# DeadHorsePCB_REV-A.net
KiCad netlist of a schematic drawn in EAGLE
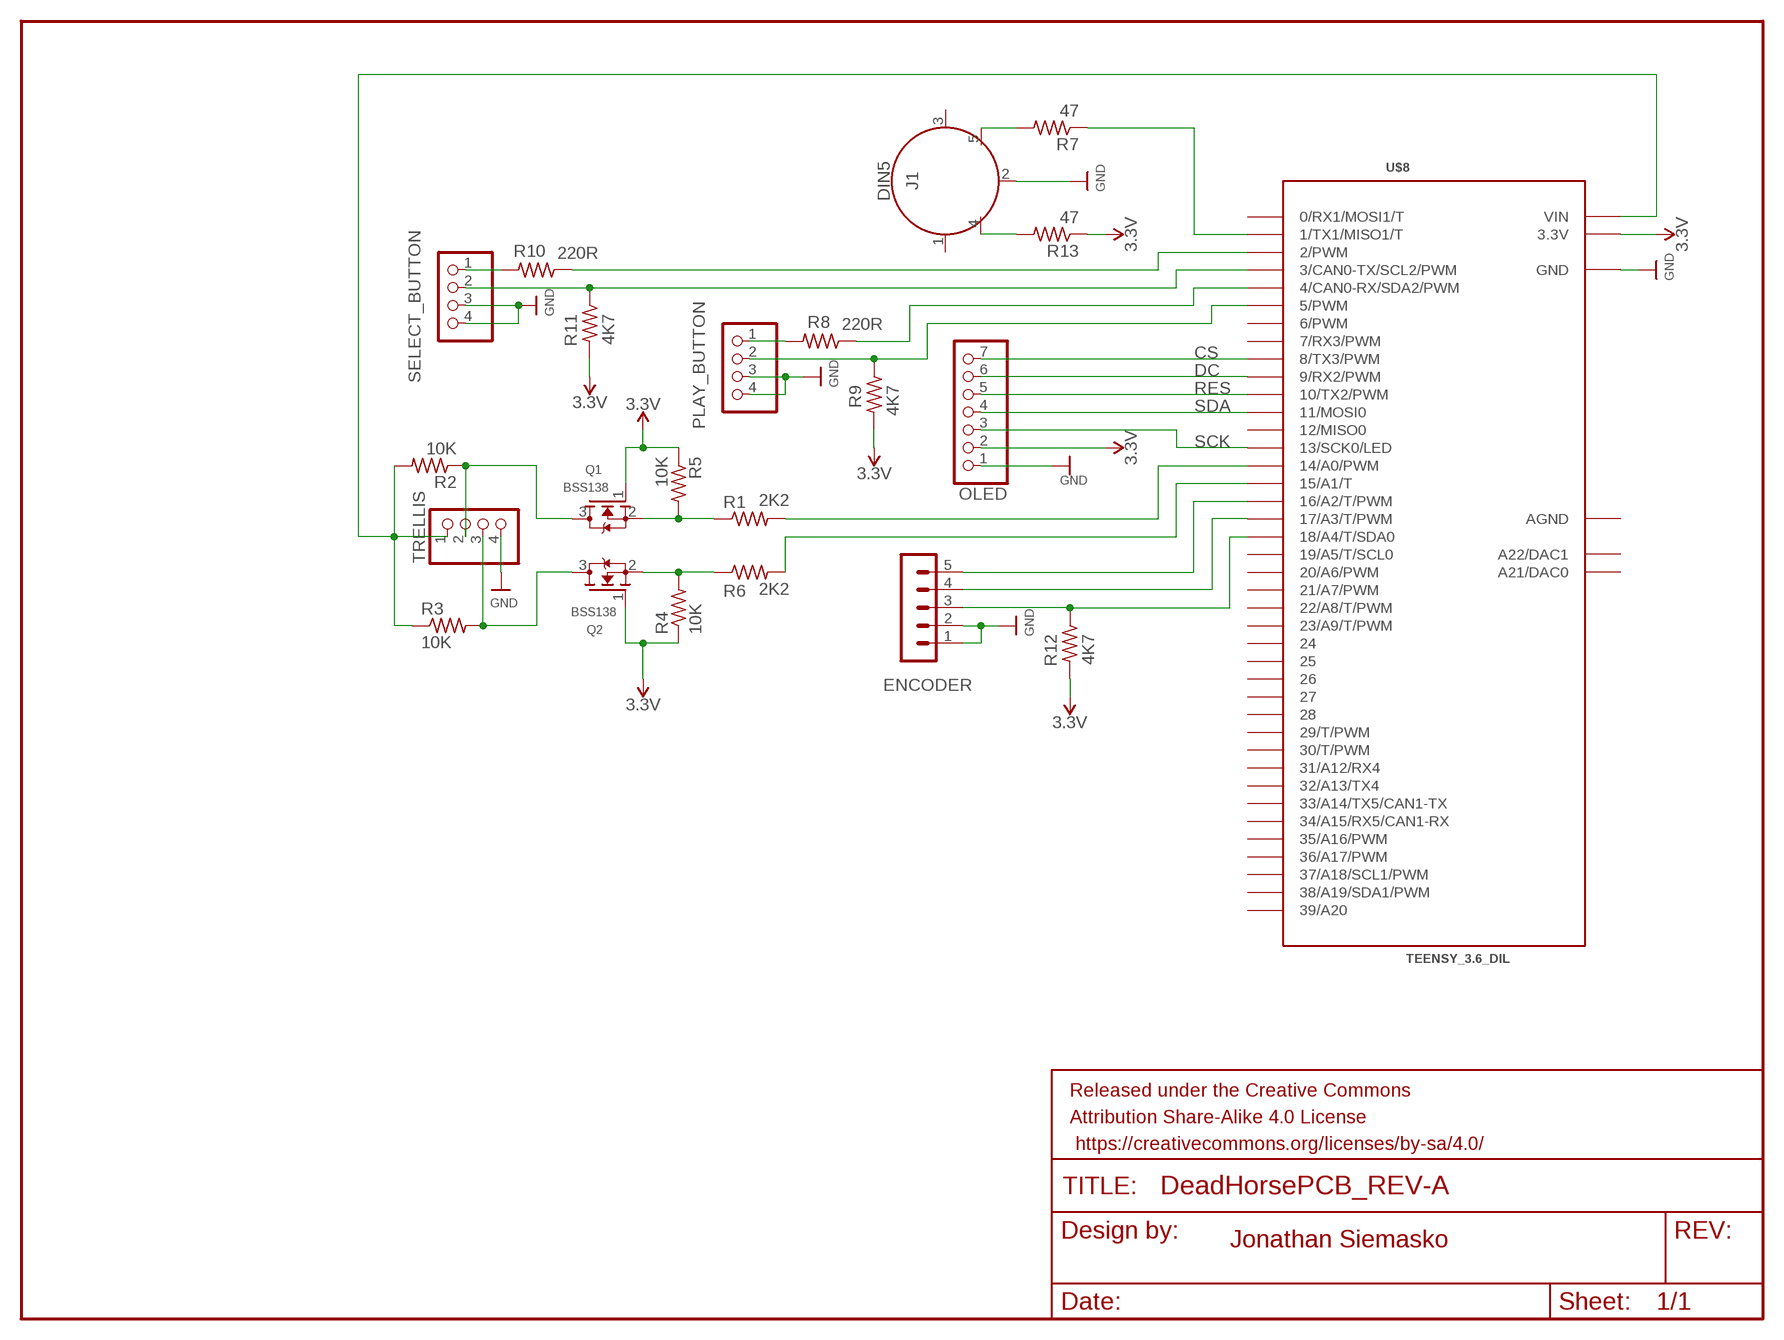
[diagram p0: schematic, sheet 1]

(export (version "E")
  (design (tool "Eeschema 10.0.6"))
  (components
    (comp (ref "ENCODER")
      (value "ENCODER")
      (footprint "eagle-import:MA05-1")
      (libsource (lib "eagle-import") (part "MA05-1"))
    )
    (comp (ref "FRAME1")
      (value "FRAME-LETTER")
      (footprint "eagle-import:CREATIVE_COMMONS")
      (libsource (lib "eagle-import") (part "FRAME-LETTER"))
    )
    (comp (ref "J1")
      (value "DIN5")
      (footprint "eagle-import:DIN5-RA-PTH")
      (libsource (lib "eagle-import") (part "DIN5"))
    )
    (comp (ref "OLED")
      (value "OLED")
      (footprint "eagle-import:1X07")
      (libsource (lib "eagle-import") (part "PINHD-1X7"))
    )
    (comp (ref "PLAY_BUTTON")
      (value "PlayBtn")
      (footprint "eagle-import:1X04")
      (libsource (lib "eagle-import") (part "PINHD-1X4"))
    )
    (comp (ref "Q1")
      (value "BSS138")
      (footprint "eagle-import:SOT23")
      (libsource (lib "eagle-import") (part "MOSFET-NREFLOW"))
    )
    (comp (ref "Q2")
      (value "BSS138")
      (footprint "eagle-import:SOT23")
      (libsource (lib "eagle-import") (part "MOSFET-NREFLOW"))
    )
    (comp (ref "R1")
      (value "2K2")
      (footprint "eagle-import:R0805")
      (libsource (lib "eagle-import") (part "R-US_R0805"))
    )
    (comp (ref "R2")
      (value "10K")
      (footprint "eagle-import:R0805")
      (libsource (lib "eagle-import") (part "R-US_R0805"))
    )
    (comp (ref "R3")
      (value "10K")
      (footprint "eagle-import:R0805")
      (libsource (lib "eagle-import") (part "R-US_R0805"))
    )
    (comp (ref "R4")
      (value "10K")
      (footprint "eagle-import:R0805")
      (libsource (lib "eagle-import") (part "R-US_R0805"))
    )
    (comp (ref "R5")
      (value "10K")
      (footprint "eagle-import:R0805")
      (libsource (lib "eagle-import") (part "R-US_R0805"))
    )
    (comp (ref "R6")
      (value "2K2")
      (footprint "eagle-import:R0805")
      (libsource (lib "eagle-import") (part "R-US_R0805"))
    )
    (comp (ref "R7")
      (value "47")
      (footprint "eagle-import:R0805")
      (libsource (lib "eagle-import") (part "R-US_R0805"))
    )
    (comp (ref "R8")
      (value "220R")
      (footprint "eagle-import:R0805")
      (libsource (lib "eagle-import") (part "R-US_R0805"))
    )
    (comp (ref "R9")
      (value "4K7")
      (footprint "eagle-import:R0805")
      (libsource (lib "eagle-import") (part "R-US_R0805"))
    )
    (comp (ref "R10")
      (value "220R")
      (footprint "eagle-import:R0805")
      (libsource (lib "eagle-import") (part "R-US_R0805"))
    )
    (comp (ref "R11")
      (value "4K7")
      (footprint "eagle-import:R0805")
      (libsource (lib "eagle-import") (part "R-US_R0805"))
    )
    (comp (ref "R12")
      (value "4K7")
      (footprint "eagle-import:R0805")
      (libsource (lib "eagle-import") (part "R-US_R0805"))
    )
    (comp (ref "R13")
      (value "47")
      (footprint "eagle-import:R0805")
      (libsource (lib "eagle-import") (part "R-US_R0805"))
    )
    (comp (ref "SELECT_BUTTON")
      (value "SelectBtn")
      (footprint "eagle-import:1X04")
      (libsource (lib "eagle-import") (part "PINHD-1X4"))
    )
    (comp (ref "TRELLIS")
      (value "TRELLIS")
      (footprint "eagle-import:1X04")
      (libsource (lib "eagle-import") (part "PINHD-1X4"))
    )
    (comp (ref "U$8")
      (value "TEENSY_3.6_DIL")
      (footprint "eagle-import:TEENSY_3.6_DIL")
      (libsource (lib "eagle-import") (part "TEENSY_3.6_DIL"))
    )
  )
  (nets
    (net (code "1") (name "/AGND") (class "Default")
      (node (ref "U$8") (pin "AGND") (pinfunction "AGND_AGND") (pintype "power_in"))
    )
    (net (code "2") (name "/CS") (class "Default")
      (node (ref "OLED") (pin "7") (pinfunction "7_7") (pintype "passive"))
      (node (ref "U$8") (pin "8") (pinfunction "8/TX3/PWM_8") (pintype "bidirectional"))
    )
    (net (code "3") (name "/DC") (class "Default")
      (node (ref "OLED") (pin "6") (pinfunction "6_6") (pintype "passive"))
      (node (ref "U$8") (pin "9") (pinfunction "9/RX2/PWM_9") (pintype "bidirectional"))
    )
    (net (code "4") (name "/RES") (class "Default")
      (node (ref "OLED") (pin "5") (pinfunction "5_5") (pintype "passive"))
      (node (ref "U$8") (pin "10") (pinfunction "10/TX2/PWM_10") (pintype "bidirectional"))
    )
    (net (code "5") (name "/SCK") (class "Default")
      (node (ref "OLED") (pin "3") (pinfunction "3_3") (pintype "passive"))
      (node (ref "U$8") (pin "13") (pinfunction "13/SCK0/LED_13") (pintype "bidirectional"))
    )
    (net (code "6") (name "/SDA") (class "Default")
      (node (ref "OLED") (pin "4") (pinfunction "4_4") (pintype "passive"))
      (node (ref "U$8") (pin "11") (pinfunction "11/MOSI0_11") (pintype "bidirectional"))
    )
    (net (code "7") (name "3.3V") (class "Default")
      (node (ref "OLED") (pin "2") (pinfunction "2_2") (pintype "passive"))
      (node (ref "Q1") (pin "1") (pinfunction "G_1") (pintype "bidirectional"))
      (node (ref "Q2") (pin "1") (pinfunction "G_1") (pintype "bidirectional"))
      (node (ref "R11") (pin "2") (pinfunction "2_2") (pintype "passive"))
      (node (ref "R12") (pin "2") (pinfunction "2_2") (pintype "passive"))
      (node (ref "R13") (pin "1") (pinfunction "1_1") (pintype "passive"))
      (node (ref "R4") (pin "1") (pinfunction "1_1") (pintype "passive"))
      (node (ref "R5") (pin "1") (pinfunction "1_1") (pintype "passive"))
      (node (ref "R9") (pin "2") (pinfunction "2_2") (pintype "passive"))
      (node (ref "U$8") (pin "3.3V") (pinfunction "3.3V_3.3V") (pintype "power_in"))
      (node (ref "U$8") (pin "3.3V3") (pinfunction "3.3V_3.3V3") (pintype "power_in"))
    )
    (net (code "8") (name "GND") (class "Default")
      (node (ref "ENCODER") (pin "1") (pinfunction "1_1") (pintype "passive"))
      (node (ref "ENCODER") (pin "2") (pinfunction "2_2") (pintype "passive"))
      (node (ref "J1") (pin "2") (pinfunction "2_2") (pintype "bidirectional"))
      (node (ref "OLED") (pin "1") (pinfunction "1_1") (pintype "passive"))
      (node (ref "PLAY_BUTTON") (pin "3") (pinfunction "3_3") (pintype "passive"))
      (node (ref "PLAY_BUTTON") (pin "4") (pinfunction "4_4") (pintype "passive"))
      (node (ref "SELECT_BUTTON") (pin "3") (pinfunction "3_3") (pintype "passive"))
      (node (ref "SELECT_BUTTON") (pin "4") (pinfunction "4_4") (pintype "passive"))
      (node (ref "TRELLIS") (pin "4") (pinfunction "4_4") (pintype "passive"))
      (node (ref "U$8") (pin "GND") (pinfunction "GND_GND") (pintype "power_in"))
      (node (ref "U$8") (pin "GND1") (pinfunction "GND_GND1") (pintype "power_in"))
    )
    (net (code "9") (name "Net-(J1-Pad4)") (class "Default")
      (node (ref "J1") (pin "4") (pinfunction "4_4") (pintype "bidirectional"))
      (node (ref "R13") (pin "2") (pinfunction "2_2") (pintype "passive"))
    )
    (net (code "10") (name "Net-(J1-Pad5)") (class "Default")
      (node (ref "J1") (pin "5") (pinfunction "5_5") (pintype "bidirectional"))
      (node (ref "R7") (pin "2") (pinfunction "2_2") (pintype "passive"))
    )
    (net (code "11") (name "Net-(PLAY_BUTTON-Pad1)") (class "Default")
      (node (ref "PLAY_BUTTON") (pin "1") (pinfunction "1_1") (pintype "passive"))
      (node (ref "R8") (pin "2") (pinfunction "2_2") (pintype "passive"))
    )
    (net (code "12") (name "Net-(Q1-D)") (class "Default")
      (node (ref "Q1") (pin "3") (pinfunction "D_3") (pintype "bidirectional"))
      (node (ref "R2") (pin "1") (pinfunction "1_1") (pintype "passive"))
      (node (ref "TRELLIS") (pin "2") (pinfunction "2_2") (pintype "passive"))
    )
    (net (code "13") (name "Net-(Q1-S)") (class "Default")
      (node (ref "Q1") (pin "2") (pinfunction "S_2") (pintype "bidirectional"))
      (node (ref "R1") (pin "1") (pinfunction "1_1") (pintype "passive"))
      (node (ref "R5") (pin "2") (pinfunction "2_2") (pintype "passive"))
    )
    (net (code "14") (name "Net-(Q2-D)") (class "Default")
      (node (ref "Q2") (pin "3") (pinfunction "D_3") (pintype "bidirectional"))
      (node (ref "R3") (pin "2") (pinfunction "2_2") (pintype "passive"))
      (node (ref "TRELLIS") (pin "3") (pinfunction "3_3") (pintype "passive"))
    )
    (net (code "15") (name "Net-(Q2-S)") (class "Default")
      (node (ref "Q2") (pin "2") (pinfunction "S_2") (pintype "bidirectional"))
      (node (ref "R4") (pin "2") (pinfunction "2_2") (pintype "passive"))
      (node (ref "R6") (pin "1") (pinfunction "1_1") (pintype "passive"))
    )
    (net (code "16") (name "Net-(R2-Pad2)") (class "Default")
      (node (ref "R2") (pin "2") (pinfunction "2_2") (pintype "passive"))
      (node (ref "R3") (pin "1") (pinfunction "1_1") (pintype "passive"))
      (node (ref "TRELLIS") (pin "1") (pinfunction "1_1") (pintype "passive"))
      (node (ref "U$8") (pin "VIN") (pinfunction "VIN_VIN") (pintype "power_in"))
    )
    (net (code "17") (name "Net-(R10-Pad2)") (class "Default")
      (node (ref "R10") (pin "2") (pinfunction "2_2") (pintype "passive"))
      (node (ref "SELECT_BUTTON") (pin "1") (pinfunction "1_1") (pintype "passive"))
    )
    (net (code "18") (name "Net-(U$8-1{slash}TX1{slash}MISO1{slash}T)") (class "Default")
      (node (ref "R7") (pin "1") (pinfunction "1_1") (pintype "passive"))
      (node (ref "U$8") (pin "1") (pinfunction "1/TX1/MISO1/T_1") (pintype "bidirectional"))
    )
    (net (code "19") (name "Net-(U$8-2{slash}PWM)") (class "Default")
      (node (ref "R10") (pin "1") (pinfunction "1_1") (pintype "passive"))
      (node (ref "U$8") (pin "2") (pinfunction "2/PWM_2") (pintype "bidirectional"))
    )
    (net (code "20") (name "Net-(U$8-3{slash}CAN0-TX{slash}SCL2{slash}PWM)") (class "Default")
      (node (ref "R11") (pin "1") (pinfunction "1_1") (pintype "passive"))
      (node (ref "SELECT_BUTTON") (pin "2") (pinfunction "2_2") (pintype "passive"))
      (node (ref "U$8") (pin "3") (pinfunction "3/CAN0-TX/SCL2/PWM_3") (pintype "bidirectional"))
    )
    (net (code "21") (name "Net-(U$8-4{slash}CAN0-RX{slash}SDA2{slash}PWM)") (class "Default")
      (node (ref "R8") (pin "1") (pinfunction "1_1") (pintype "passive"))
      (node (ref "U$8") (pin "4") (pinfunction "4/CAN0-RX/SDA2/PWM_4") (pintype "bidirectional"))
    )
    (net (code "22") (name "Net-(U$8-5{slash}PWM)") (class "Default")
      (node (ref "PLAY_BUTTON") (pin "2") (pinfunction "2_2") (pintype "passive"))
      (node (ref "R9") (pin "1") (pinfunction "1_1") (pintype "passive"))
      (node (ref "U$8") (pin "5") (pinfunction "5/PWM_5") (pintype "bidirectional"))
    )
    (net (code "23") (name "Net-(U$8-14{slash}A0{slash}PWM)") (class "Default")
      (node (ref "R1") (pin "2") (pinfunction "2_2") (pintype "passive"))
      (node (ref "U$8") (pin "14/A0") (pinfunction "14/A0/PWM_14/A0") (pintype "bidirectional"))
    )
    (net (code "24") (name "Net-(U$8-15{slash}A1{slash}T)") (class "Default")
      (node (ref "R6") (pin "2") (pinfunction "2_2") (pintype "passive"))
      (node (ref "U$8") (pin "15/A1") (pinfunction "15/A1/T_15/A1") (pintype "bidirectional"))
    )
    (net (code "25") (name "Net-(U$8-16{slash}A2{slash}T{slash}PWM)") (class "Default")
      (node (ref "ENCODER") (pin "5") (pinfunction "5_5") (pintype "passive"))
      (node (ref "U$8") (pin "16/A2") (pinfunction "16/A2/T/PWM_16/A2") (pintype "bidirectional"))
    )
    (net (code "26") (name "Net-(U$8-17{slash}A3{slash}T{slash}PWM)") (class "Default")
      (node (ref "ENCODER") (pin "4") (pinfunction "4_4") (pintype "passive"))
      (node (ref "U$8") (pin "17/A3") (pinfunction "17/A3/T/PWM_17/A3") (pintype "bidirectional"))
    )
    (net (code "27") (name "Net-(U$8-18{slash}A4{slash}T{slash}SDA0)") (class "Default")
      (node (ref "ENCODER") (pin "3") (pinfunction "3_3") (pintype "passive"))
      (node (ref "R12") (pin "1") (pinfunction "1_1") (pintype "passive"))
      (node (ref "U$8") (pin "18/A4") (pinfunction "18/A4/T/SDA0_18/A4") (pintype "bidirectional"))
    )
    (net (code "28") (name "unconnected-(J1-Pad1)") (class "Default")
      (node (ref "J1") (pin "1") (pinfunction "1_1") (pintype "bidirectional"))
    )
    (net (code "29") (name "unconnected-(J1-Pad3)") (class "Default")
      (node (ref "J1") (pin "3") (pinfunction "3_3") (pintype "bidirectional"))
    )
    (net (code "30") (name "unconnected-(U$8-0{slash}RX1{slash}MOSI1{slash}T-Pad0)") (class "Default")
      (node (ref "U$8") (pin "0") (pinfunction "0/RX1/MOSI1/T_0") (pintype "bidirectional"))
    )
    (net (code "31") (name "unconnected-(U$8-6{slash}PWM-Pad6)") (class "Default")
      (node (ref "U$8") (pin "6") (pinfunction "6/PWM_6") (pintype "bidirectional"))
    )
    (net (code "32") (name "unconnected-(U$8-7{slash}RX3{slash}PWM-Pad7)") (class "Default")
      (node (ref "U$8") (pin "7") (pinfunction "7/RX3/PWM_7") (pintype "bidirectional"))
    )
    (net (code "33") (name "unconnected-(U$8-12{slash}MISO0-Pad12)") (class "Default")
      (node (ref "U$8") (pin "12") (pinfunction "12/MISO0_12") (pintype "bidirectional"))
    )
    (net (code "34") (name "unconnected-(U$8-19{slash}A5{slash}T{slash}SCL0-Pad19{slash}A5)") (class "Default")
      (node (ref "U$8") (pin "19/A5") (pinfunction "19/A5/T/SCL0_19/A5") (pintype "bidirectional"))
    )
    (net (code "35") (name "unconnected-(U$8-20{slash}A6{slash}PWM-Pad20{slash}A6)") (class "Default")
      (node (ref "U$8") (pin "20/A6") (pinfunction "20/A6/PWM_20/A6") (pintype "bidirectional"))
    )
    (net (code "36") (name "unconnected-(U$8-21{slash}A7{slash}PWM-Pad21{slash}A7)") (class "Default")
      (node (ref "U$8") (pin "21/A7") (pinfunction "21/A7/PWM_21/A7") (pintype "bidirectional"))
    )
    (net (code "37") (name "unconnected-(U$8-22{slash}A8{slash}T{slash}PWM-Pad22{slash}A8)") (class "Default")
      (node (ref "U$8") (pin "22/A8") (pinfunction "22/A8/T/PWM_22/A8") (pintype "bidirectional"))
    )
    (net (code "38") (name "unconnected-(U$8-23{slash}A9{slash}T{slash}PWM-Pad23{slash}A9)") (class "Default")
      (node (ref "U$8") (pin "23/A9") (pinfunction "23/A9/T/PWM_23/A9") (pintype "bidirectional"))
    )
    (net (code "39") (name "unconnected-(U$8-29{slash}T{slash}PWM-Pad29)") (class "Default")
      (node (ref "U$8") (pin "29") (pinfunction "29/T/PWM_29") (pintype "bidirectional"))
    )
    (net (code "40") (name "unconnected-(U$8-30{slash}T{slash}PWM-Pad30)") (class "Default")
      (node (ref "U$8") (pin "30") (pinfunction "30/T/PWM_30") (pintype "bidirectional"))
    )
    (net (code "41") (name "unconnected-(U$8-31{slash}A12{slash}RX4-Pad31{slash}A12)") (class "Default")
      (node (ref "U$8") (pin "31/A12") (pinfunction "31/A12/RX4_31/A12") (pintype "bidirectional"))
    )
    (net (code "42") (name "unconnected-(U$8-32{slash}A13{slash}TX4-Pad32{slash}A13)") (class "Default")
      (node (ref "U$8") (pin "32/A13") (pinfunction "32/A13/TX4_32/A13") (pintype "bidirectional"))
    )
    (net (code "43") (name "unconnected-(U$8-33{slash}A14{slash}TX5{slash}CAN1-TX-Pad33{slash}A14)") (class "Default")
      (node (ref "U$8") (pin "33/A14") (pinfunction "33/A14/TX5/CAN1-TX_33/A14") (pintype "bidirectional"))
    )
    (net (code "44") (name "unconnected-(U$8-34{slash}A15{slash}RX5{slash}CAN1-RX-Pad34{slash}A15)") (class "Default")
      (node (ref "U$8") (pin "34/A15") (pinfunction "34/A15/RX5/CAN1-RX_34/A15") (pintype "bidirectional"))
    )
    (net (code "45") (name "unconnected-(U$8-35{slash}A16{slash}PWM-Pad35{slash}A16)") (class "Default")
      (node (ref "U$8") (pin "35/A16") (pinfunction "35/A16/PWM_35/A16") (pintype "bidirectional"))
    )
    (net (code "46") (name "unconnected-(U$8-36{slash}A17{slash}PWM-Pad36{slash}A17)") (class "Default")
      (node (ref "U$8") (pin "36/A17") (pinfunction "36/A17/PWM_36/A17") (pintype "bidirectional"))
    )
    (net (code "47") (name "unconnected-(U$8-37{slash}A18{slash}SCL1{slash}PWM-Pad37{slash}A18)") (class "Default")
      (node (ref "U$8") (pin "37/A18") (pinfunction "37/A18/SCL1/PWM_37/A18") (pintype "bidirectional"))
    )
    (net (code "48") (name "unconnected-(U$8-38{slash}A19{slash}SDA1{slash}PWM-Pad38{slash}A19)") (class "Default")
      (node (ref "U$8") (pin "38/A19") (pinfunction "38/A19/SDA1/PWM_38/A19") (pintype "bidirectional"))
    )
    (net (code "49") (name "unconnected-(U$8-A21{slash}DAC0-PadA21)") (class "Default")
      (node (ref "U$8") (pin "A21") (pinfunction "A21/DAC0_A21") (pintype "bidirectional"))
    )
    (net (code "50") (name "unconnected-(U$8-A22{slash}DAC1-PadA22)") (class "Default")
      (node (ref "U$8") (pin "A22") (pinfunction "A22/DAC1_A22") (pintype "bidirectional"))
    )
    (net (code "51") (name "unconnected-(U$8-Pad24)") (class "Default")
      (node (ref "U$8") (pin "24") (pinfunction "24_24") (pintype "bidirectional"))
    )
    (net (code "52") (name "unconnected-(U$8-Pad25)") (class "Default")
      (node (ref "U$8") (pin "25") (pinfunction "25_25") (pintype "bidirectional"))
    )
    (net (code "53") (name "unconnected-(U$8-Pad26)") (class "Default")
      (node (ref "U$8") (pin "26") (pinfunction "26_26") (pintype "bidirectional"))
    )
    (net (code "54") (name "unconnected-(U$8-Pad27)") (class "Default")
      (node (ref "U$8") (pin "27") (pinfunction "27_27") (pintype "bidirectional"))
    )
    (net (code "55") (name "unconnected-(U$8-Pad28)") (class "Default")
      (node (ref "U$8") (pin "28") (pinfunction "28_28") (pintype "bidirectional"))
    )
    (net (code "56") (name "unconnected-(U$8-Pad39{slash}A20)") (class "Default")
      (node (ref "U$8") (pin "39/A20") (pinfunction "39/A20_39/A20") (pintype "bidirectional"))
    )
  )
)
